# Storage.net
KiCad netlist of a schematic drawn in Altium Designer
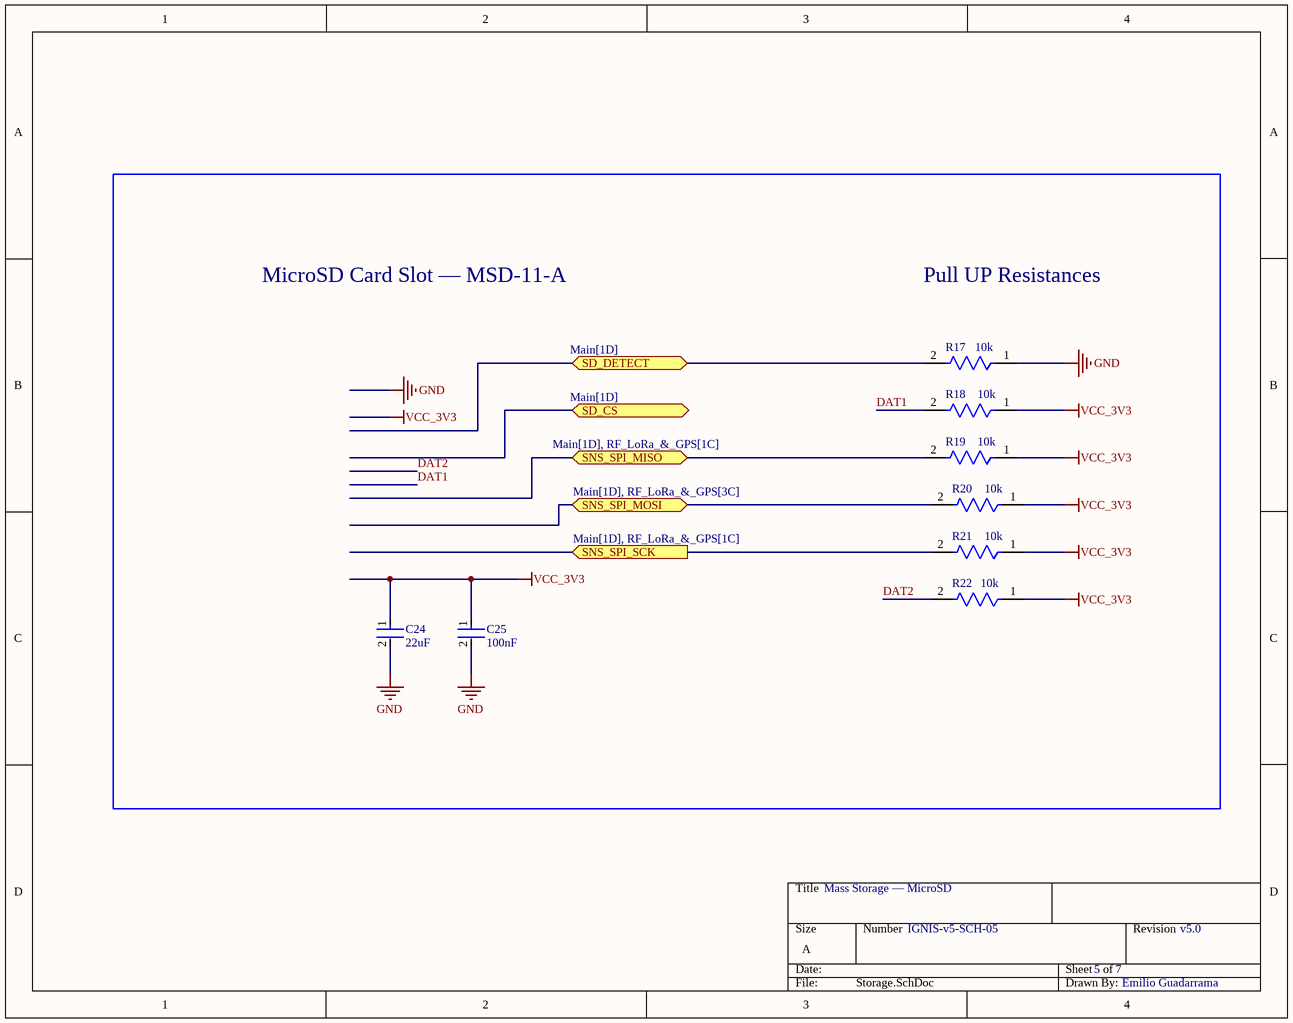
[diagram p0: Storage.SchDoc]

(export (version "E")
  (design (tool "Eeschema 10.0.6"))
  (components
    (comp (ref "C24")
      (value "22uF")
      (footprint "FP-C0805C-DN-MFG")
      (description "CAP CER 0.1UF 50V X7R 0805")
      (fields
        (field (name "MANUFACTURER PART NUMBER") "C0805C104K5RACTU")
        (field (name "MANUFACTURER") "KEMET")
      )
      (libsource (lib "Altium Content Vault") (part "b4654b650e69147ec39a6b967a45e02"))
    )
    (comp (ref "C25")
      (value "100nF")
      (footprint "FP-C0805C-DN-MFG")
      (description "CAP CER 0.1UF 50V X7R 0805")
      (fields
        (field (name "MANUFACTURER PART NUMBER") "C0805C104K5RACTU")
        (field (name "MANUFACTURER") "KEMET")
      )
      (libsource (lib "Altium Content Vault") (part "b4654b650e69147ec39a6b967a45e02"))
    )
    (comp (ref "R17")
      (value "10k")
      (footprint "FP-MCT0603-IPC_A")
      (description "RES SMD 100 OHM 1% 1/8W 0603")
      (fields (field (name "TOLERANCE") "0.1%"))
      (libsource (lib "Altium Content Vault") (part "1029c3af85768c4190bb7ad29bc67b5"))
    )
    (comp (ref "R18")
      (value "10k")
      (footprint "FP-MCT0603-IPC_A")
      (description "RES SMD 100 OHM 1% 1/8W 0603")
      (fields (field (name "TOLERANCE") "0.1%"))
      (libsource (lib "Altium Content Vault") (part "1029c3af85768c4190bb7ad29bc67b5"))
    )
    (comp (ref "R19")
      (value "10k")
      (footprint "FP-MCT0603-IPC_A")
      (description "RES SMD 100 OHM 1% 1/8W 0603")
      (fields (field (name "TOLERANCE") "0.1%"))
      (libsource (lib "Altium Content Vault") (part "1029c3af85768c4190bb7ad29bc67b5"))
    )
    (comp (ref "R20")
      (value "10k")
      (footprint "FP-MCT0603-IPC_A")
      (description "RES SMD 100 OHM 1% 1/8W 0603")
      (fields (field (name "TOLERANCE") "0.1%"))
      (libsource (lib "Altium Content Vault") (part "1029c3af85768c4190bb7ad29bc67b5"))
    )
    (comp (ref "R21")
      (value "10k")
      (footprint "FP-MCT0603-IPC_A")
      (description "RES SMD 100 OHM 1% 1/8W 0603")
      (fields (field (name "TOLERANCE") "0.1%"))
      (libsource (lib "Altium Content Vault") (part "1029c3af85768c4190bb7ad29bc67b5"))
    )
    (comp (ref "R22")
      (value "10k")
      (footprint "FP-MCT0603-IPC_A")
      (description "RES SMD 100 OHM 1% 1/8W 0603")
      (fields (field (name "TOLERANCE") "0.1%"))
      (libsource (lib "Altium Content Vault") (part "1029c3af85768c4190bb7ad29bc67b5"))
    )
  )
  (nets
    (net (code "1") (name "/DAT1") (class "Default")
      (node (ref "R18") (pin "2") (pinfunction "2_2") (pintype "passive"))
    )
    (net (code "2") (name "/DAT2") (class "Default")
      (node (ref "R22") (pin "2") (pinfunction "2_2") (pintype "passive"))
    )
    (net (code "4") (name "/SD_DETECT") (class "Default")
      (node (ref "R17") (pin "2") (pinfunction "2_2") (pintype "passive"))
    )
    (net (code "5") (name "/SNS_SPI_MISO") (class "Default")
      (node (ref "R19") (pin "2") (pinfunction "2_2") (pintype "passive"))
    )
    (net (code "6") (name "/SNS_SPI_MOSI") (class "Default")
      (node (ref "R20") (pin "2") (pinfunction "2_2") (pintype "passive"))
    )
    (net (code "7") (name "/SNS_SPI_SCK") (class "Default")
      (node (ref "R21") (pin "2") (pinfunction "2_2") (pintype "passive"))
    )
    (net (code "8") (name "GND") (class "Default")
      (node (ref "C24") (pin "2") (pinfunction "2_2") (pintype "passive"))
      (node (ref "C25") (pin "2") (pinfunction "2_2") (pintype "passive"))
      (node (ref "R17") (pin "1") (pinfunction "1_1") (pintype "passive"))
    )
    (net (code "9") (name "VCC_3V3") (class "Default")
      (node (ref "C24") (pin "1") (pinfunction "1_1") (pintype "passive"))
      (node (ref "C25") (pin "1") (pinfunction "1_1") (pintype "passive"))
      (node (ref "R18") (pin "1") (pinfunction "1_1") (pintype "passive"))
      (node (ref "R19") (pin "1") (pinfunction "1_1") (pintype "passive"))
      (node (ref "R20") (pin "1") (pinfunction "1_1") (pintype "passive"))
      (node (ref "R21") (pin "1") (pinfunction "1_1") (pintype "passive"))
      (node (ref "R22") (pin "1") (pinfunction "1_1") (pintype "passive"))
    )
  )
)
